# load-sw.net
KiCad netlist of a schematic drawn in Altium Designer
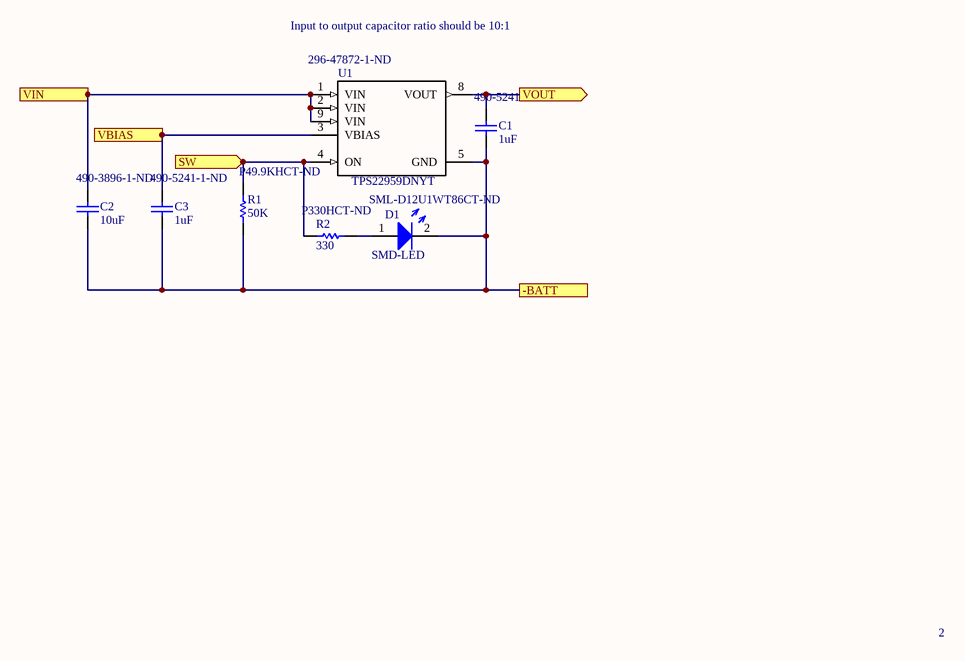
[diagram p0: load-sw.SchDoc]

(export (version "E")
  (design (tool "Eeschema 10.0.6"))
  (components
    (comp (ref "C1")
      (value "1uF")
      (footprint "1608[0603]")
      (description "Capacitor (Semiconductor SIM Model)")
      (fields
        (field (name "SUPPLIER PART NUMBER 1") "490-5241-1-ND")
        (field (name "MANUFACTURER") "Murata")
        (field (name "MANUFACTURER PART NUMBER") "GCM188R71C105KA64D")
        (field (name "PUBLISHER") "Altium Limited")
      )
      (libsource (lib "Miscellaneous Devices") (part "Cap Semi"))
    )
    (comp (ref "C2")
      (value "10uF")
      (footprint "1608[0603]")
      (description "Capacitor (Semiconductor SIM Model)")
      (fields
        (field (name "SUPPLIER PART NUMBER 1") "490-3896-1-ND")
        (field (name "MANUFACTURER") "Murata")
        (field (name "MANUFACTURER PART NUMBER") "GRM188R60J106ME47D")
        (field (name "PUBLISHER") "Altium Limited")
      )
      (libsource (lib "Miscellaneous Devices") (part "Cap Semi"))
    )
    (comp (ref "C3")
      (value "1uF")
      (footprint "1608[0603]")
      (description "Capacitor (Semiconductor SIM Model)")
      (fields
        (field (name "SUPPLIER PART NUMBER 1") "490-5241-1-ND")
        (field (name "MANUFACTURER") "Murata")
        (field (name "MANUFACTURER PART NUMBER") "GCM188R71C105KA64D")
        (field (name "PUBLISHER") "Altium Limited")
      )
      (libsource (lib "Miscellaneous Devices") (part "Cap Semi"))
    )
    (comp (ref "D1")
      (value "SMD-LED")
      (footprint "0603-LED")
      (description "Just a generic LED")
      (fields
        (field (name "SUPPLIER PART NUMBER 1") "SML-D12U1WT86CT-ND")
        (field (name "MANUFACTURER") "Rohm")
        (field (name "MANUFACTURER PART NUMBER") "SML-D12U1WT86")
      )
      (libsource (lib "heron-general") (part "LED"))
    )
    (comp (ref "R1")
      (value "50K")
      (footprint "1608[0603]")
      (description "Resistor")
      (fields
        (field (name "SUPPLIER PART NUMBER 1") "P49.9KHCT-ND")
        (field (name "MANUFACTURER") "Panasonic")
        (field (name "MANUFACTURER PART NUMBER") "ERJ3EKF4992V")
        (field (name "PUBLISHER") "Altium Limited")
      )
      (libsource (lib "Miscellaneous Devices") (part "Res1"))
    )
    (comp (ref "R2")
      (value "330")
      (footprint "1608[0603]")
      (description "Resistor")
      (fields
        (field (name "SUPPLIER PART NUMBER 1") "P330HCT-ND")
        (field (name "MANUFACTURER") "Panasonic")
        (field (name "MANUFACTURER PART NUMBER") "ERJ3EKF3300V")
        (field (name "PUBLISHER") "Altium Limited")
      )
      (libsource (lib "Miscellaneous Devices") (part "Res1"))
    )
    (comp (ref "U1")
      (value "TPS22959DNYT")
      (footprint "TPS22959DNYT")
      (description "5.5V, 15A, 4.4mÎ© Load Switch with Quick Output Discharge 8-WSON -40 to 85")
      (fields
        (field (name "MF") "Texas Instruments")
        (field (name "DIGI-KEY_PART_NUMBER") "296-47872-1-ND")
        (field (name "SUPPLIER PART NUMBER 1") "296-47872-1-ND")
      )
      (libsource (lib "heron-general") (part "TPS22959DNYT"))
    )
  )
  (nets
    (net (code "1") (name "/-BATT") (class "Default")
      (node (ref "C1") (pin "1") (pinfunction "1_1") (pintype "passive"))
      (node (ref "C2") (pin "1") (pinfunction "1_1") (pintype "passive"))
      (node (ref "C3") (pin "1") (pinfunction "1_1") (pintype "passive"))
      (node (ref "D1") (pin "2") (pinfunction "2_2") (pintype "passive"))
      (node (ref "R1") (pin "1") (pinfunction "1_1") (pintype "passive"))
      (node (ref "U1") (pin "5") (pinfunction "GND_5") (pintype "power_in"))
    )
    (net (code "2") (name "/SW") (class "Default")
      (node (ref "R1") (pin "2") (pinfunction "2_2") (pintype "passive"))
      (node (ref "R2") (pin "2") (pinfunction "2_2") (pintype "passive"))
      (node (ref "U1") (pin "4") (pinfunction "ON_4") (pintype "input"))
    )
    (net (code "3") (name "/VBIAS") (class "Default")
      (node (ref "C3") (pin "2") (pinfunction "2_2") (pintype "passive"))
      (node (ref "U1") (pin "3") (pinfunction "VBIAS_3") (pintype "power_in"))
    )
    (net (code "4") (name "/VIN") (class "Default")
      (node (ref "C2") (pin "2") (pinfunction "2_2") (pintype "passive"))
      (node (ref "U1") (pin "1") (pinfunction "VIN_1") (pintype "input"))
      (node (ref "U1") (pin "2") (pinfunction "VIN_2") (pintype "input"))
      (node (ref "U1") (pin "9") (pinfunction "VIN_9") (pintype "input"))
    )
    (net (code "5") (name "/VOUT") (class "Default")
      (node (ref "C1") (pin "2") (pinfunction "2_2") (pintype "passive"))
      (node (ref "U1") (pin "8") (pinfunction "VOUT_8") (pintype "output"))
    )
    (net (code "6") (name "Net-(D1-Pad1)") (class "Default")
      (node (ref "D1") (pin "1") (pinfunction "1_1") (pintype "passive"))
      (node (ref "R2") (pin "1") (pinfunction "1_1") (pintype "passive"))
    )
  )
)
